# Power_Supply_2.net
KiCad netlist of a schematic drawn in Altium Designer
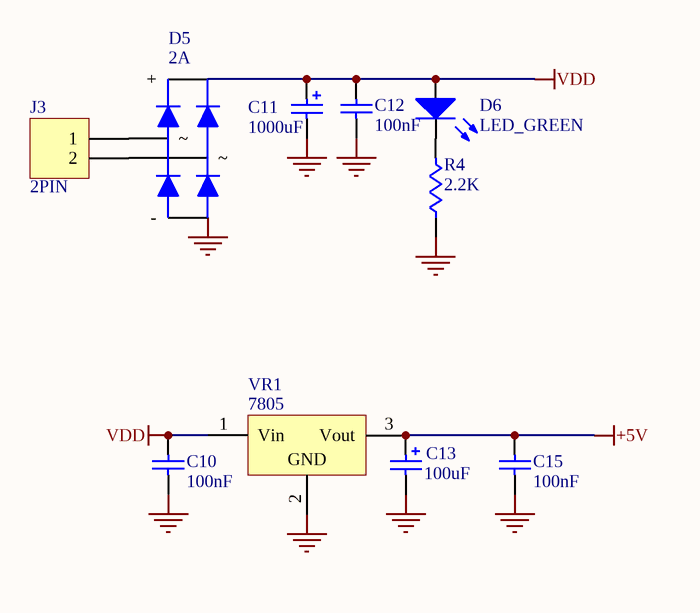
[diagram p0: Power Supply_2.SchDoc]

(export (version "E")
  (design (tool "Eeschema 10.0.6"))
  (components
    (comp (ref "C10")
      (value "100nF")
      (footprint "CAPNTO2.54-3.05x1.78A")
      (description "Capacitor")
      (fields (field (name "MANUFACTURER") "Generic Components") (field (name "PUBLISHER") "Altium Limited"))
      (libsource (lib "Miscellaneous Devices") (part "Cap"))
    )
    (comp (ref "C11")
      (value "1000uF")
      (footprint "CAPPR5-10x12.5")
      (description "Polarized Capacitor (Radial)")
      (fields (field (name "MANUFACTURER") "Generic Components") (field (name "PUBLISHER") "Altium Limited"))
      (libsource (lib "Miscellaneous Devices") (part "Cap Pol1"))
    )
    (comp (ref "C12")
      (value "100nF")
      (footprint "CAPNTO2.54-3.05x1.78A")
      (description "Capacitor")
      (fields (field (name "MANUFACTURER") "Generic Components") (field (name "PUBLISHER") "Altium Limited"))
      (libsource (lib "Miscellaneous Devices") (part "Cap"))
    )
    (comp (ref "C13")
      (value "100uF")
      (footprint "CAPPR2.5-6.3x5")
      (description "Polarized Capacitor (Radial)")
      (fields (field (name "MANUFACTURER") "Generic Components") (field (name "PUBLISHER") "Altium Limited"))
      (libsource (lib "Miscellaneous Devices") (part "Cap Pol1"))
    )
    (comp (ref "C15")
      (value "100nF")
      (footprint "CAPNTO2.54-3.05x1.78A")
      (description "Capacitor")
      (fields (field (name "MANUFACTURER") "Generic Components") (field (name "PUBLISHER") "Altium Limited"))
      (libsource (lib "Miscellaneous Devices") (part "Cap"))
    )
    (comp (ref "D5")
      (value "2A")
      (footprint "BRIDGE-1")
      (description "Full Wave Diode Bridge")
      (fields (field (name "MANUFACTURER") "Generic Components") (field (name "PUBLISHER") "Altium Limited"))
      (libsource (lib "my Libraries") (part "Bridge_1"))
    )
    (comp (ref "D6")
      (value "LED_GREEN")
      (footprint "LED-5mm_Red")
      (description "Typical INFRARED GaAs LED")
      (fields (field (name "MANUFACTURER") "Generic Components") (field (name "PUBLISHER") "Altium Limited"))
      (libsource (lib "Miscellaneous Devices") (part "LED"))
    )
    (comp (ref "J3")
      (value "2PIN")
      (footprint "Fonics_2PIN_1")
      (description "Header, 2-Pin")
      (fields (field (name "PUBLISHER") "Altium Limited"))
      (libsource (lib "Miscellaneous Connectors") (part "Header 2"))
    )
    (comp (ref "R4")
      (value "2.2K")
      (footprint "AXIAL-0.4")
      (description "Resistor")
      (fields (field (name "MANUFACTURER") "Generic Components") (field (name "PUBLISHER") "Altium Limited"))
      (libsource (lib "Miscellaneous Devices") (part "Res1"))
    )
    (comp (ref "VR1")
      (value "7805")
      (footprint "TO220V")
      (description "Voltage Regulator")
      (fields (field (name "MANUFACTURER") "Generic Components") (field (name "PUBLISHER") "Altium Limited"))
      (libsource (lib "my Libraries") (part "Volt Reg"))
    )
  )
  (nets
    (net (code "1") (name "+5V") (class "Default")
      (node (ref "C13") (pin "1") (pinfunction "1_1") (pintype "passive"))
      (node (ref "C15") (pin "2") (pinfunction "2_2") (pintype "passive"))
      (node (ref "VR1") (pin "3") (pinfunction "Vout_3") (pintype "passive"))
    )
    (net (code "2") (name "GND") (class "Default")
      (node (ref "C10") (pin "1") (pinfunction "1_1") (pintype "passive"))
      (node (ref "C11") (pin "2") (pinfunction "2_2") (pintype "passive"))
      (node (ref "C12") (pin "1") (pinfunction "1_1") (pintype "passive"))
      (node (ref "C13") (pin "2") (pinfunction "2_2") (pintype "passive"))
      (node (ref "C15") (pin "1") (pinfunction "1_1") (pintype "passive"))
      (node (ref "D5") (pin "1") (pinfunction "-_1") (pintype "passive"))
      (node (ref "R4") (pin "1") (pinfunction "1_1") (pintype "passive"))
      (node (ref "VR1") (pin "2") (pinfunction "GND_2") (pintype "passive"))
    )
    (net (code "3") (name "Net-(D5-~-Pad2)") (class "Default")
      (node (ref "D5") (pin "2") (pinfunction "~_2") (pintype "passive"))
      (node (ref "J3") (pin "2") (pinfunction "2_2") (pintype "passive"))
    )
    (net (code "4") (name "Net-(D5-~-Pad4)") (class "Default")
      (node (ref "D5") (pin "4") (pinfunction "~_4") (pintype "passive"))
      (node (ref "J3") (pin "1") (pinfunction "1_1") (pintype "passive"))
    )
    (net (code "5") (name "Net-(D6-K)") (class "Default")
      (node (ref "D6") (pin "2") (pinfunction "K_2") (pintype "passive"))
      (node (ref "R4") (pin "2") (pinfunction "2_2") (pintype "passive"))
    )
    (net (code "6") (name "VDD") (class "Default")
      (node (ref "C10") (pin "2") (pinfunction "2_2") (pintype "passive"))
      (node (ref "C11") (pin "1") (pinfunction "1_1") (pintype "passive"))
      (node (ref "C12") (pin "2") (pinfunction "2_2") (pintype "passive"))
      (node (ref "D5") (pin "3") (pinfunction "+_3") (pintype "passive"))
      (node (ref "D6") (pin "1") (pinfunction "A_1") (pintype "passive"))
      (node (ref "VR1") (pin "1") (pinfunction "Vin_1") (pintype "passive"))
    )
  )
)
